# TempPres.net
KiCad netlist of a schematic drawn in Altium Designer
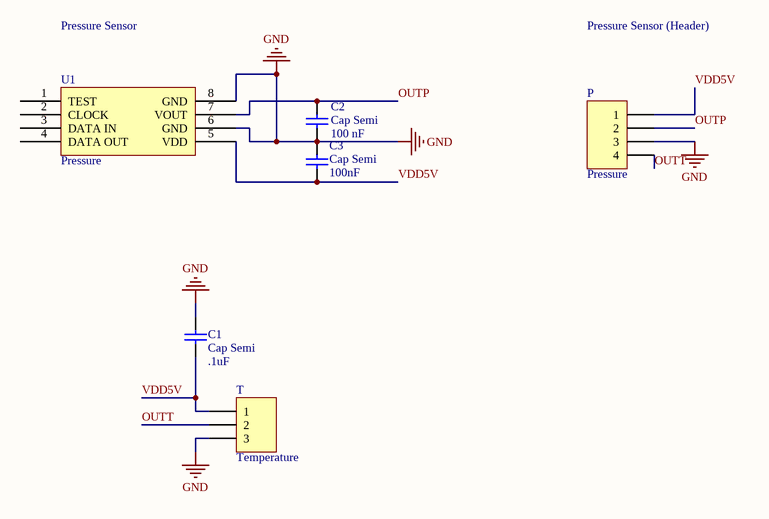
[diagram p0: TempPres.SchDoc]

(export (version "E")
  (design (tool "Eeschema 10.0.6"))
  (components
    (comp (ref "C1")
      (value "Cap Semi")
      (footprint "C1206")
      (description "Capacitor (Semiconductor SIM Model)")
      (fields (field (name "ALTIUM_VALUE") ".1uF") (field (name "PUBLISHER") "Altium Limited"))
      (libsource (lib "Miscellaneous Devices") (part "Cap Semi"))
    )
    (comp (ref "C2")
      (value "Cap Semi")
      (footprint "C1206")
      (description "Capacitor (Semiconductor SIM Model)")
      (fields (field (name "ALTIUM_VALUE") "100 nF") (field (name "PUBLISHER") "Altium Limited"))
      (libsource (lib "Miscellaneous Devices") (part "Cap Semi"))
    )
    (comp (ref "C3")
      (value "Cap Semi")
      (footprint "C1206")
      (description "Capacitor (Semiconductor SIM Model)")
      (fields (field (name "ALTIUM_VALUE") "100nF") (field (name "PUBLISHER") "Altium Limited"))
      (libsource (lib "Miscellaneous Devices") (part "Cap Semi"))
    )
    (comp (ref "P")
      (value "Pressure")
      (footprint "HDR1X4")
      (description "Header, 4-Pin, Right Angle")
      (fields (field (name "PUBLISHER") "Altium Limited"))
      (libsource (lib "Miscellaneous Connectors") (part "Header 4H"))
    )
    (comp (ref "T")
      (value "Temperature")
      (footprint "HDR1X3")
      (description "Header, 3-Pin")
      (fields (field (name "PUBLISHER") "Altium Limited"))
      (libsource (lib "Miscellaneous Connectors") (part "Header 3"))
    )
    (comp (ref "U1") (value "Pressure") (footprint "KP-234") (libsource (lib "KP234") (part "Component_1")))
  )
  (nets
    (net (code "1") (name "/OUTP") (class "Default")
      (node (ref "C2") (pin "2") (pinfunction "2_2") (pintype "passive"))
      (node (ref "P") (pin "2") (pinfunction "2_2") (pintype "passive"))
      (node (ref "U1") (pin "7") (pinfunction "VOUT_7") (pintype "passive"))
    )
    (net (code "2") (name "/OUTT") (class "Default")
      (node (ref "P") (pin "4") (pinfunction "4_4") (pintype "passive"))
      (node (ref "T") (pin "2") (pinfunction "2_2") (pintype "passive"))
    )
    (net (code "3") (name "/VDD5V") (class "Default")
      (node (ref "C1") (pin "1") (pinfunction "1_1") (pintype "passive"))
      (node (ref "C3") (pin "1") (pinfunction "1_1") (pintype "passive"))
      (node (ref "P") (pin "1") (pinfunction "1_1") (pintype "passive"))
      (node (ref "T") (pin "1") (pinfunction "1_1") (pintype "passive"))
      (node (ref "U1") (pin "5") (pinfunction "VDD_5") (pintype "passive"))
    )
    (net (code "4") (name "GND") (class "Default")
      (node (ref "C1") (pin "2") (pinfunction "2_2") (pintype "passive"))
      (node (ref "C2") (pin "1") (pinfunction "1_1") (pintype "passive"))
      (node (ref "C3") (pin "2") (pinfunction "2_2") (pintype "passive"))
      (node (ref "P") (pin "3") (pinfunction "3_3") (pintype "passive"))
      (node (ref "T") (pin "3") (pinfunction "3_3") (pintype "passive"))
      (node (ref "U1") (pin "6") (pinfunction "GND_6") (pintype "passive"))
      (node (ref "U1") (pin "8") (pinfunction "GND_8") (pintype "passive"))
    )
    (net (code "5") (name "unconnected-(U1-CLOCK-Pad2)") (class "Default")
      (node (ref "U1") (pin "2") (pinfunction "CLOCK_2") (pintype "passive"))
    )
    (net (code "6") (name "unconnected-(U1-DATA_IN-Pad3)") (class "Default")
      (node (ref "U1") (pin "3") (pinfunction "DATA_IN_3") (pintype "passive"))
    )
    (net (code "7") (name "unconnected-(U1-DATA_OUT-Pad4)") (class "Default")
      (node (ref "U1") (pin "4") (pinfunction "DATA_OUT_4") (pintype "passive"))
    )
    (net (code "8") (name "unconnected-(U1-TEST-Pad1)") (class "Default")
      (node (ref "U1") (pin "1") (pinfunction "TEST_1") (pintype "passive"))
    )
  )
)
